# Brduino-PwrLin.net
KiCad netlist of a schematic drawn in Altium Designer
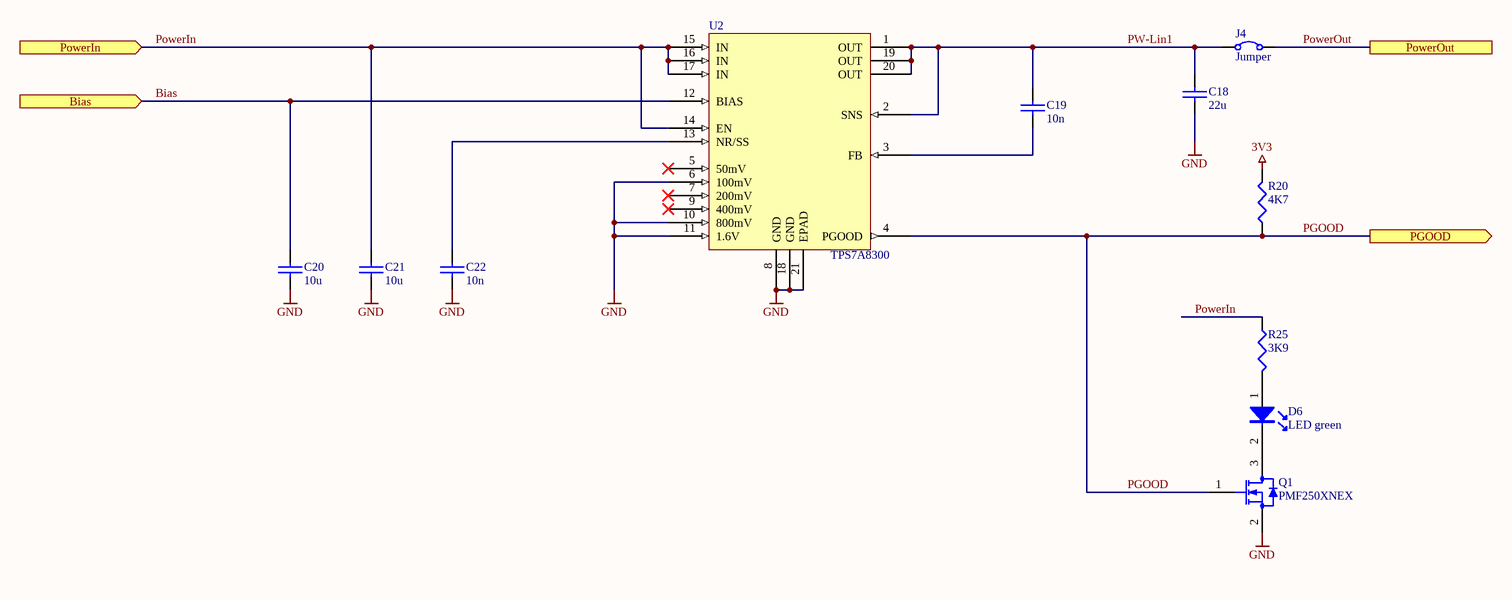
[diagram p0: Brduino-PwrLin.SchDoc]

(export (version "E")
  (design (tool "Eeschema 10.0.6"))
  (components
    (comp (ref "C18")
      (value "22u")
      (footprint "C0805")
      (fields (field (name "MFR") "MURATA"))
      (libsource (lib "UCP250") (part "CAP"))
    )
    (comp (ref "C19")
      (value "10n")
      (footprint "C0402")
      (fields (field (name "MFR") "MURATA"))
      (libsource (lib "SchLib1") (part "CAP"))
    )
    (comp (ref "C20")
      (value "10u")
      (footprint "C0805")
      (fields (field (name "MFR") "MURATA"))
      (libsource (lib "UCP250") (part "CAP"))
    )
    (comp (ref "C21")
      (value "10u")
      (footprint "C0805")
      (fields (field (name "MFR") "MURATA"))
      (libsource (lib "UCP250") (part "CAP"))
    )
    (comp (ref "C22")
      (value "10n")
      (footprint "C0402")
      (fields (field (name "MFR") "MURATA"))
      (libsource (lib "VideoDemo") (part "CAP"))
    )
    (comp (ref "D6")
      (value "LED green")
      (footprint "LED0603")
      (fields (field (name "MFR") "KINGBRIGHT"))
      (libsource (lib "SchLib1") (part "LED"))
    )
    (comp (ref "J4") (value "Jumper") (footprint "JumperSMD") (libsource (lib "VideoDemo1") (part "Jumper")))
    (comp (ref "Q1")
      (value "PMF250XNEX")
      (footprint "SOT323")
      (description "N-Channel MOSFET")
      (fields (field (name "MFR") "NEXPERIA"))
      (libsource (lib "SchLib1") (part "MOSFET-N-D"))
    )
    (comp (ref "R20") (value "4K7") (footprint "R0402") (libsource (lib "VideoDemo") (part "RES1A")))
    (comp (ref "R25") (value "3K9") (footprint "R0402") (libsource (lib "SchLib1") (part "RES1A")))
    (comp (ref "U2")
      (value "TPS7A8300")
      (footprint "S-PVQFN-N20")
      (fields (field (name "MFR") "TI"))
      (libsource (lib "SchLib1") (part "TPS7A8300"))
    )
  )
  (nets
    (net (code "1") (name "/Bias") (class "Default")
      (node (ref "C20") (pin "2") (pinfunction "2_2") (pintype "passive"))
      (node (ref "U2") (pin "12") (pinfunction "BIAS_12") (pintype "input"))
    )
    (net (code "2") (name "/PGOOD") (class "Default")
      (node (ref "Q1") (pin "1") (pinfunction "G_1") (pintype "passive"))
      (node (ref "R20") (pin "1") (pinfunction "1_1") (pintype "passive"))
      (node (ref "U2") (pin "4") (pinfunction "PGOOD_4") (pintype "output"))
    )
    (net (code "3") (name "/PW-Lin1") (class "Default")
      (node (ref "C18") (pin "2") (pinfunction "2_2") (pintype "passive"))
      (node (ref "C19") (pin "1") (pinfunction "1_1") (pintype "passive"))
      (node (ref "J4") (pin "1") (pinfunction "1_1") (pintype "passive"))
      (node (ref "U2") (pin "1") (pinfunction "OUT_1") (pintype "tri_state"))
      (node (ref "U2") (pin "19") (pinfunction "OUT_19") (pintype "tri_state"))
      (node (ref "U2") (pin "2") (pinfunction "SNS_2") (pintype "input"))
      (node (ref "U2") (pin "20") (pinfunction "OUT_20") (pintype "tri_state"))
    )
    (net (code "4") (name "/PowerIn") (class "Default")
      (node (ref "C21") (pin "2") (pinfunction "2_2") (pintype "passive"))
      (node (ref "R25") (pin "1") (pinfunction "1_1") (pintype "passive"))
      (node (ref "U2") (pin "14") (pinfunction "EN_14") (pintype "input"))
      (node (ref "U2") (pin "15") (pinfunction "IN_15") (pintype "input"))
      (node (ref "U2") (pin "16") (pinfunction "IN_16") (pintype "input"))
      (node (ref "U2") (pin "17") (pinfunction "IN_17") (pintype "input"))
    )
    (net (code "5") (name "/PowerOut") (class "Default")
      (node (ref "J4") (pin "2") (pinfunction "2_2") (pintype "passive"))
    )
    (net (code "6") (name "3V3") (class "Default")
      (node (ref "R20") (pin "2") (pinfunction "2_2") (pintype "passive"))
    )
    (net (code "7") (name "GND") (class "Default")
      (node (ref "C18") (pin "1") (pinfunction "1_1") (pintype "passive"))
      (node (ref "C20") (pin "1") (pinfunction "1_1") (pintype "passive"))
      (node (ref "C21") (pin "1") (pinfunction "1_1") (pintype "passive"))
      (node (ref "C22") (pin "2") (pinfunction "2_2") (pintype "passive"))
      (node (ref "Q1") (pin "2") (pinfunction "S_2") (pintype "passive"))
      (node (ref "U2") (pin "10") (pinfunction "800mV_10") (pintype "input"))
      (node (ref "U2") (pin "11") (pinfunction "1.6V_11") (pintype "input"))
      (node (ref "U2") (pin "18") (pinfunction "GND_18") (pintype "power_in"))
      (node (ref "U2") (pin "21") (pinfunction "EPAD_21") (pintype "passive"))
      (node (ref "U2") (pin "6") (pinfunction "100mV_6") (pintype "input"))
      (node (ref "U2") (pin "8") (pinfunction "GND_8") (pintype "power_in"))
    )
    (net (code "8") (name "Net-(D6-A)") (class "Default")
      (node (ref "D6") (pin "1") (pinfunction "A_1") (pintype "passive"))
      (node (ref "R25") (pin "2") (pinfunction "2_2") (pintype "passive"))
    )
    (net (code "9") (name "Net-(D6-K)") (class "Default")
      (node (ref "D6") (pin "2") (pinfunction "K_2") (pintype "passive"))
      (node (ref "Q1") (pin "3") (pinfunction "D_3") (pintype "passive"))
    )
    (net (code "10") (name "Net-(U2-FB)") (class "Default")
      (node (ref "C19") (pin "2") (pinfunction "2_2") (pintype "passive"))
      (node (ref "U2") (pin "3") (pinfunction "FB_3") (pintype "input"))
    )
    (net (code "11") (name "Net-(U2-NR{slash}SS)") (class "Default")
      (node (ref "C22") (pin "1") (pinfunction "1_1") (pintype "passive"))
      (node (ref "U2") (pin "13") (pinfunction "NR/SS_13") (pintype "input"))
    )
    (net (code "12") (name "unconnected-(U2-50mV-Pad5)") (class "Default")
      (node (ref "U2") (pin "5") (pinfunction "50mV_5") (pintype "input+no_connect"))
    )
    (net (code "13") (name "unconnected-(U2-200mV-Pad7)") (class "Default")
      (node (ref "U2") (pin "7") (pinfunction "200mV_7") (pintype "input+no_connect"))
    )
    (net (code "14") (name "unconnected-(U2-400mV-Pad9)") (class "Default")
      (node (ref "U2") (pin "9") (pinfunction "400mV_9") (pintype "input+no_connect"))
    )
  )
)
